# io-pack-3-3.net
KiCad netlist of a schematic drawn in EAGLE
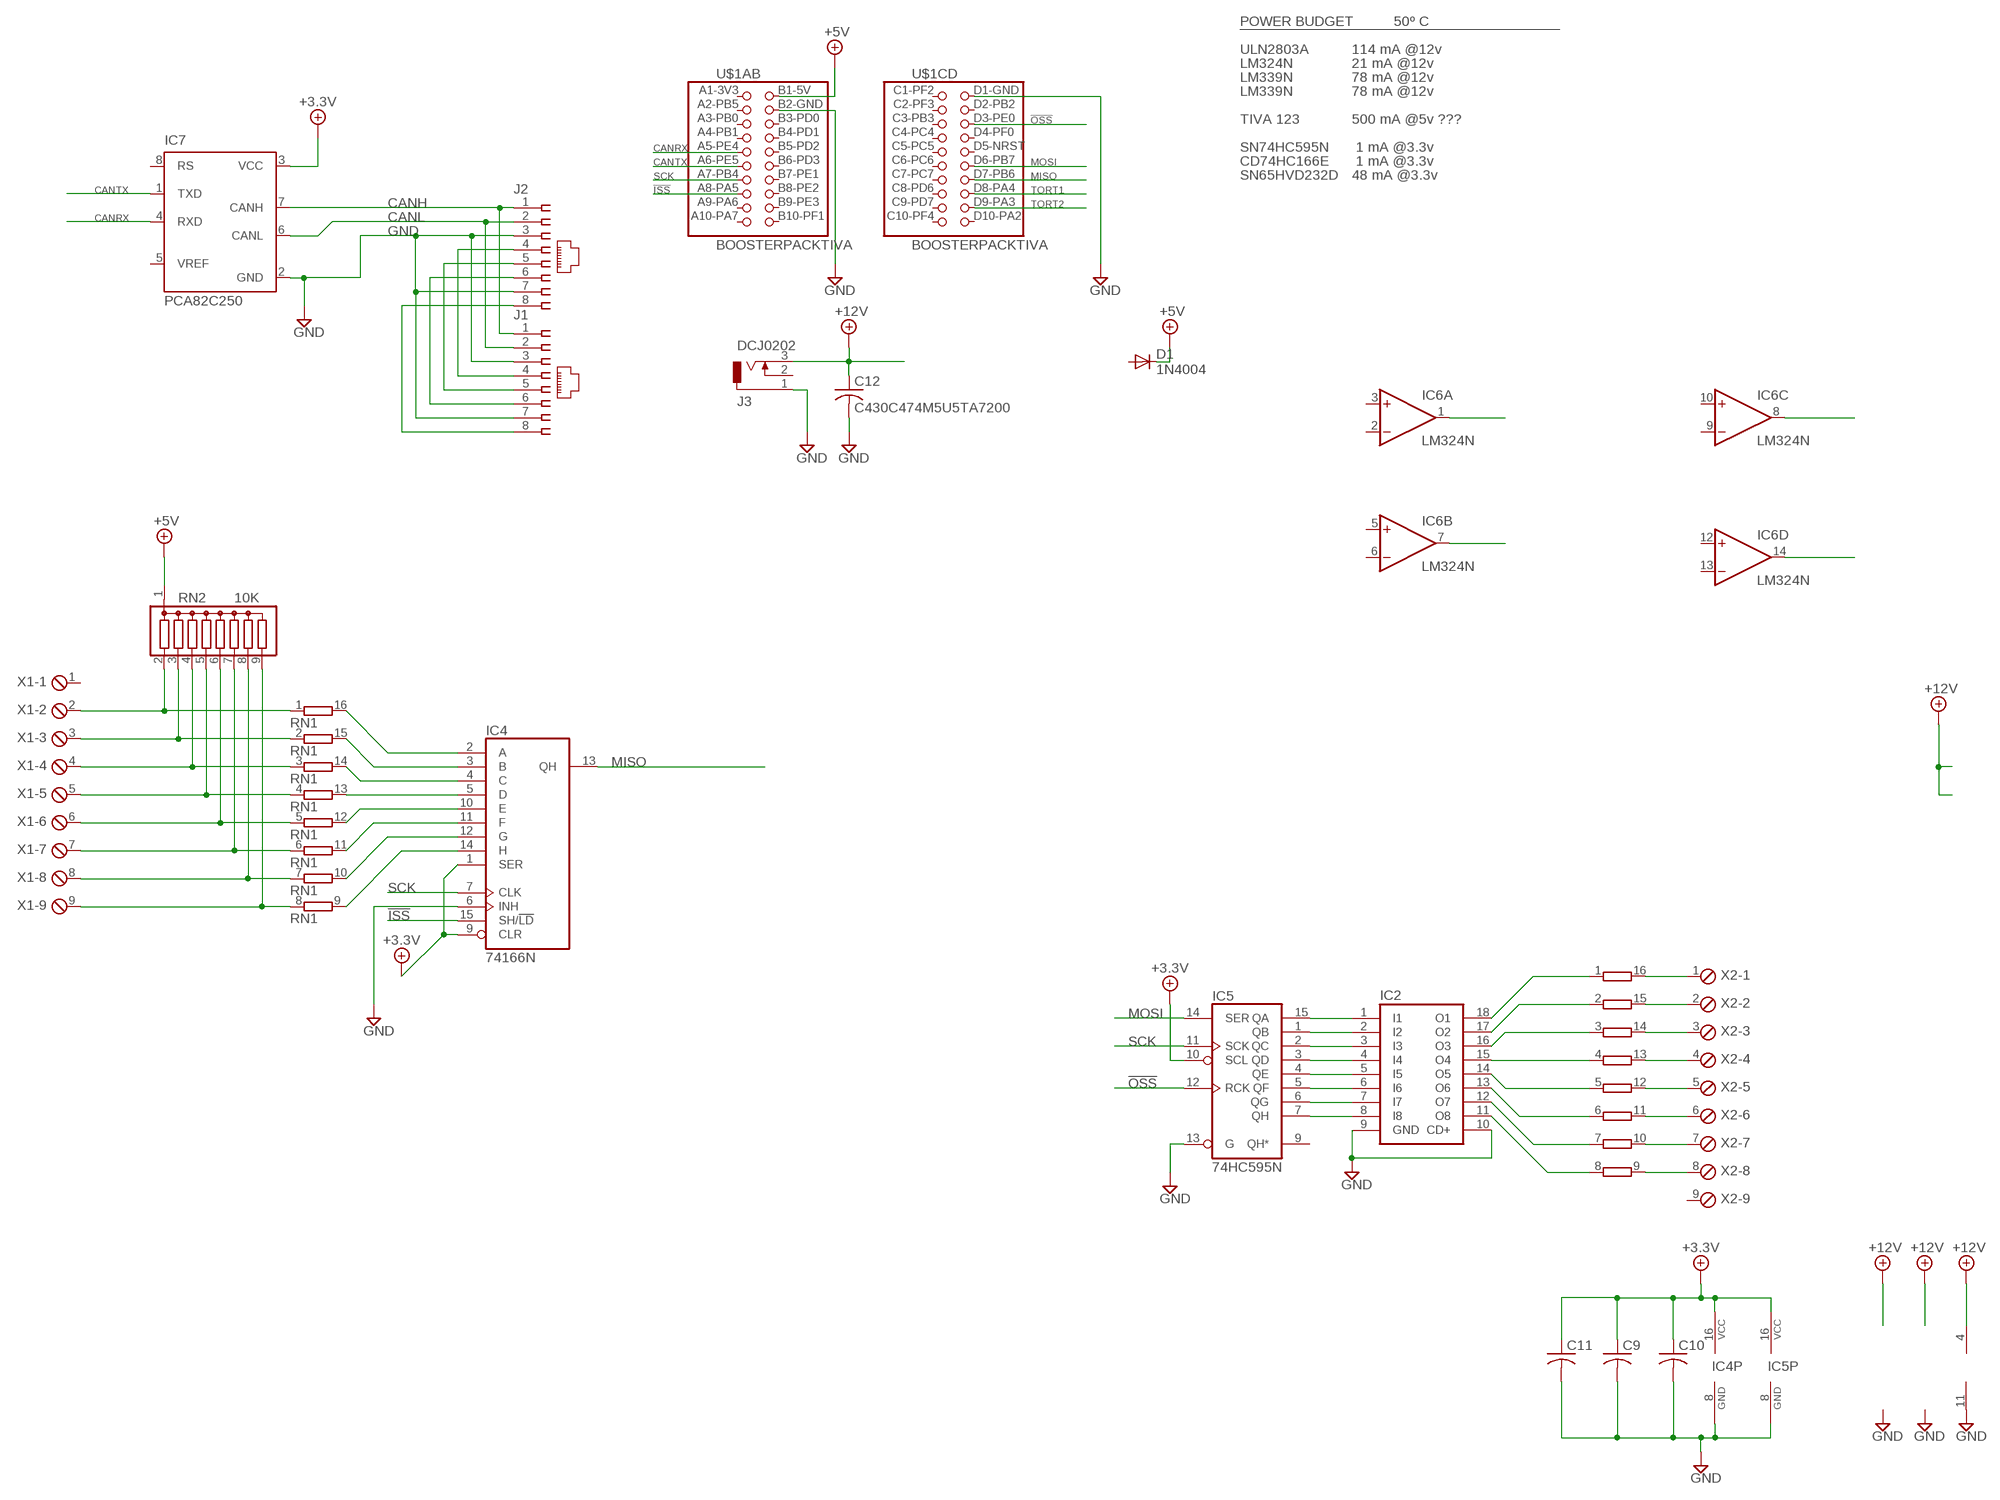
[diagram p0: schematic, sheet 1]

(export (version "E")
  (design (tool "Eeschema 10.0.6"))
  (components
    (comp (ref "C9")
      (value "C-US050-025X075")
      (footprint "eagle-import:C050-025X075")
      (libsource (lib "eagle-import") (part "C-US050-025X075"))
    )
    (comp (ref "C10")
      (value "C-US050-025X075")
      (footprint "eagle-import:C050-025X075")
      (libsource (lib "eagle-import") (part "C-US050-025X075"))
    )
    (comp (ref "C11")
      (value "C-US050-025X075")
      (footprint "eagle-import:C050-025X075")
      (libsource (lib "eagle-import") (part "C-US050-025X075"))
    )
    (comp (ref "C12")
      (value "C430C474M5U5TA7200")
      (footprint "eagle-import:C075-032X103")
      (libsource (lib "eagle-import") (part "C-US075-032X103"))
    )
    (comp (ref "D1")
      (value "1N4004")
      (footprint "eagle-import:DO41-10")
      (libsource (lib "eagle-import") (part "1N4004"))
    )
    (comp (ref "IC2")
      (value "ULN2803A")
      (footprint "eagle-import:DIL18")
      (libsource (lib "eagle-import") (part "ULN2803A"))
    )
    (comp (ref "IC4")
      (value "74166N")
      (footprint "eagle-import:DIL16")
      (libsource (lib "eagle-import") (part "74166N"))
    )
    (comp (ref "IC5")
      (value "74HC595N")
      (footprint "eagle-import:DIL16")
      (libsource (lib "eagle-import") (part "74595NLS"))
    )
    (comp (ref "IC6")
      (value "LM324N")
      (footprint "eagle-import:DIL14")
      (libsource (lib "eagle-import") (part "LM324N"))
    )
    (comp (ref "IC7")
      (value "PCA82C250")
      (footprint "eagle-import:DIL08")
      (libsource (lib "eagle-import") (part "PCA82C250"))
    )
    (comp (ref "J1")
      (value "555164-1")
      (footprint "eagle-import:555164-1")
      (libsource (lib "eagle-import") (part "555164-1"))
    )
    (comp (ref "J2")
      (value "555164-1")
      (footprint "eagle-import:555164-1")
      (libsource (lib "eagle-import") (part "555164-1"))
    )
    (comp (ref "J3")
      (value "DCJ0202")
      (footprint "eagle-import:DCJ0202")
      (libsource (lib "eagle-import") (part "DCJ0202"))
    )
    (comp (ref "RN1")
      (value "8R-P")
      (footprint "eagle-import:DIL16")
      (libsource (lib "eagle-import") (part "8R-P"))
    )
    (comp (ref "RN2")
      (value "10K")
      (footprint "eagle-import:SIL9")
      (libsource (lib "eagle-import") (part "G08R"))
    )
    (comp (ref "RN3")
      (value "8R-P")
      (footprint "eagle-import:DIL16")
      (libsource (lib "eagle-import") (part "8R-P"))
    )
    (comp (ref "U$1")
      (value "BOOSTERPACKTIVA")
      (footprint "eagle-import:BOOSTERPACK-TIVA")
      (libsource (lib "eagle-import") (part "BOOSTERPACKTIVA"))
    )
    (comp (ref "X1")
      (value "MPT9")
      (footprint "eagle-import:9POL254")
      (libsource (lib "eagle-import") (part "MPT9"))
    )
    (comp (ref "X2")
      (value "MPT9")
      (footprint "eagle-import:9POL254")
      (libsource (lib "eagle-import") (part "MPT9"))
    )
  )
  (nets
    (net (code "1") (name "+3.3V") (class "Default")
      (node (ref "C10") (pin "1") (pinfunction "1_1") (pintype "passive"))
      (node (ref "C11") (pin "1") (pinfunction "1_1") (pintype "passive"))
      (node (ref "C9") (pin "1") (pinfunction "1_1") (pintype "passive"))
      (node (ref "IC4") (pin "1") (pinfunction "SER_1") (pintype "input"))
      (node (ref "IC4") (pin "16") (pinfunction "VCC_16") (pintype "power_in"))
      (node (ref "IC4") (pin "9") (pinfunction "CLR_9") (pintype "input"))
      (node (ref "IC5") (pin "10") (pinfunction "SCL_10") (pintype "input"))
      (node (ref "IC5") (pin "16") (pinfunction "VCC_16") (pintype "power_in"))
      (node (ref "IC7") (pin "3") (pinfunction "VCC_3") (pintype "power_in"))
    )
    (net (code "2") (name "+5V") (class "Default")
      (node (ref "D1") (pin "C") (pinfunction "C_C") (pintype "passive"))
      (node (ref "RN2") (pin "1") (pinfunction "1_1") (pintype "passive"))
      (node (ref "U$1") (pin "B1-5V") (pinfunction "2_B1-5V") (pintype "passive"))
    )
    (net (code "3") (name "+12V") (class "Default")
      (node (ref "C12") (pin "1") (pinfunction "1_1") (pintype "passive"))
      (node (ref "IC6") (pin "4") (pinfunction "V+_4") (pintype "power_in"))
      (node (ref "J3") (pin "3") (pinfunction "3_3") (pintype "passive"))
    )
    (net (code "4") (name "/CANH") (class "Default")
      (node (ref "IC7") (pin "7") (pinfunction "CANH_7") (pintype "bidirectional"))
      (node (ref "J1") (pin "1") (pinfunction "1_1") (pintype "passive"))
      (node (ref "J2") (pin "1") (pinfunction "1_1") (pintype "passive"))
    )
    (net (code "5") (name "/CANL") (class "Default")
      (node (ref "IC7") (pin "6") (pinfunction "CANL_6") (pintype "bidirectional"))
      (node (ref "J1") (pin "2") (pinfunction "2_2") (pintype "passive"))
      (node (ref "J2") (pin "2") (pinfunction "2_2") (pintype "passive"))
    )
    (net (code "6") (name "/CANRX") (class "Default")
      (node (ref "IC7") (pin "4") (pinfunction "RXD_4") (pintype "output"))
      (node (ref "U$1") (pin "A5-PE4") (pinfunction "9_A5-PE4") (pintype "passive"))
    )
    (net (code "7") (name "/CANTX") (class "Default")
      (node (ref "IC7") (pin "1") (pinfunction "TXD_1") (pintype "input"))
      (node (ref "U$1") (pin "A6-PE5") (pinfunction "11_A6-PE5") (pintype "passive"))
    )
    (net (code "8") (name "/MISO") (class "Default")
      (node (ref "IC4") (pin "13") (pinfunction "QH_13") (pintype "output"))
      (node (ref "U$1") (pin "D7-PB6") (pinfunction "14_D7-PB6") (pintype "passive"))
    )
    (net (code "9") (name "/MOSI") (class "Default")
      (node (ref "IC5") (pin "14") (pinfunction "SER_14") (pintype "input"))
      (node (ref "U$1") (pin "D6-PB7") (pinfunction "12_D6-PB7") (pintype "passive"))
    )
    (net (code "10") (name "/SCK") (class "Default")
      (node (ref "IC4") (pin "7") (pinfunction "CLK_7") (pintype "input"))
      (node (ref "IC5") (pin "11") (pinfunction "SCK_11") (pintype "input"))
      (node (ref "U$1") (pin "A7-PB4") (pinfunction "13_A7-PB4") (pintype "passive"))
    )
    (net (code "11") (name "/TORT1") (class "Default")
      (node (ref "U$1") (pin "D8-PA4") (pinfunction "16_D8-PA4") (pintype "passive"))
    )
    (net (code "12") (name "/TORT2") (class "Default")
      (node (ref "U$1") (pin "D9-PA3") (pinfunction "18_D9-PA3") (pintype "passive"))
    )
    (net (code "13") (name "/~{ISS}") (class "Default")
      (node (ref "IC4") (pin "15") (pinfunction "SH/~{LD}_15") (pintype "input"))
      (node (ref "U$1") (pin "A8-PA5") (pinfunction "15_A8-PA5") (pintype "passive"))
    )
    (net (code "14") (name "/~{OSS}") (class "Default")
      (node (ref "IC5") (pin "12") (pinfunction "RCK_12") (pintype "input"))
      (node (ref "U$1") (pin "D3-PE0") (pinfunction "6_D3-PE0") (pintype "passive"))
    )
    (net (code "15") (name "GND") (class "Default")
      (node (ref "C10") (pin "2") (pinfunction "2_2") (pintype "passive"))
      (node (ref "C11") (pin "2") (pinfunction "2_2") (pintype "passive"))
      (node (ref "C12") (pin "2") (pinfunction "2_2") (pintype "passive"))
      (node (ref "C9") (pin "2") (pinfunction "2_2") (pintype "passive"))
      (node (ref "IC2") (pin "10") (pinfunction "CD+_10") (pintype "passive"))
      (node (ref "IC2") (pin "9") (pinfunction "GND_9") (pintype "power_in"))
      (node (ref "IC4") (pin "6") (pinfunction "INH_6") (pintype "input"))
      (node (ref "IC4") (pin "8") (pinfunction "GND_8") (pintype "power_in"))
      (node (ref "IC5") (pin "13") (pinfunction "G_13") (pintype "input"))
      (node (ref "IC5") (pin "8") (pinfunction "GND_8") (pintype "power_in"))
      (node (ref "IC6") (pin "11") (pinfunction "V-_11") (pintype "power_in"))
      (node (ref "IC7") (pin "2") (pinfunction "GND_2") (pintype "power_in"))
      (node (ref "J1") (pin "3") (pinfunction "3_3") (pintype "passive"))
      (node (ref "J1") (pin "7") (pinfunction "7_7") (pintype "passive"))
      (node (ref "J2") (pin "3") (pinfunction "3_3") (pintype "passive"))
      (node (ref "J2") (pin "7") (pinfunction "7_7") (pintype "passive"))
      (node (ref "J3") (pin "1") (pinfunction "1_1") (pintype "passive"))
      (node (ref "U$1") (pin "B2-GND") (pinfunction "4_B2-GND") (pintype "passive"))
      (node (ref "U$1") (pin "D1-GND") (pinfunction "2_D1-GND") (pintype "passive"))
    )
    (net (code "16") (name "Net-(IC2-I1)") (class "Default")
      (node (ref "IC2") (pin "1") (pinfunction "I1_1") (pintype "input"))
      (node (ref "IC5") (pin "15") (pinfunction "QA_15") (pintype "tri_state"))
    )
    (net (code "17") (name "Net-(IC2-I2)") (class "Default")
      (node (ref "IC2") (pin "2") (pinfunction "I2_2") (pintype "input"))
      (node (ref "IC5") (pin "1") (pinfunction "QB_1") (pintype "tri_state"))
    )
    (net (code "18") (name "Net-(IC2-I3)") (class "Default")
      (node (ref "IC2") (pin "3") (pinfunction "I3_3") (pintype "input"))
      (node (ref "IC5") (pin "2") (pinfunction "QC_2") (pintype "tri_state"))
    )
    (net (code "19") (name "Net-(IC2-I4)") (class "Default")
      (node (ref "IC2") (pin "4") (pinfunction "I4_4") (pintype "input"))
      (node (ref "IC5") (pin "3") (pinfunction "QD_3") (pintype "tri_state"))
    )
    (net (code "20") (name "Net-(IC2-I5)") (class "Default")
      (node (ref "IC2") (pin "5") (pinfunction "I5_5") (pintype "input"))
      (node (ref "IC5") (pin "4") (pinfunction "QE_4") (pintype "tri_state"))
    )
    (net (code "21") (name "Net-(IC2-I6)") (class "Default")
      (node (ref "IC2") (pin "6") (pinfunction "I6_6") (pintype "input"))
      (node (ref "IC5") (pin "5") (pinfunction "QF_5") (pintype "tri_state"))
    )
    (net (code "22") (name "Net-(IC2-I7)") (class "Default")
      (node (ref "IC2") (pin "7") (pinfunction "I7_7") (pintype "input"))
      (node (ref "IC5") (pin "6") (pinfunction "QG_6") (pintype "tri_state"))
    )
    (net (code "23") (name "Net-(IC2-I8)") (class "Default")
      (node (ref "IC2") (pin "8") (pinfunction "I8_8") (pintype "input"))
      (node (ref "IC5") (pin "7") (pinfunction "QH_7") (pintype "tri_state"))
    )
    (net (code "24") (name "Net-(IC2-O1)") (class "Default")
      (node (ref "IC2") (pin "18") (pinfunction "O1_18") (pintype "open_collector"))
      (node (ref "RN3") (pin "1") (pinfunction "1_1") (pintype "passive"))
    )
    (net (code "25") (name "Net-(IC2-O2)") (class "Default")
      (node (ref "IC2") (pin "17") (pinfunction "O2_17") (pintype "open_collector"))
      (node (ref "RN3") (pin "2") (pinfunction "1_2") (pintype "passive"))
    )
    (net (code "26") (name "Net-(IC2-O3)") (class "Default")
      (node (ref "IC2") (pin "16") (pinfunction "O3_16") (pintype "open_collector"))
      (node (ref "RN3") (pin "3") (pinfunction "1_3") (pintype "passive"))
    )
    (net (code "27") (name "Net-(IC2-O4)") (class "Default")
      (node (ref "IC2") (pin "15") (pinfunction "O4_15") (pintype "open_collector"))
      (node (ref "RN3") (pin "4") (pinfunction "1_4") (pintype "passive"))
    )
    (net (code "28") (name "Net-(IC2-O5)") (class "Default")
      (node (ref "IC2") (pin "14") (pinfunction "O5_14") (pintype "open_collector"))
      (node (ref "RN3") (pin "5") (pinfunction "1_5") (pintype "passive"))
    )
    (net (code "29") (name "Net-(IC2-O6)") (class "Default")
      (node (ref "IC2") (pin "13") (pinfunction "O6_13") (pintype "open_collector"))
      (node (ref "RN3") (pin "6") (pinfunction "1_6") (pintype "passive"))
    )
    (net (code "30") (name "Net-(IC2-O7)") (class "Default")
      (node (ref "IC2") (pin "12") (pinfunction "O7_12") (pintype "open_collector"))
      (node (ref "RN3") (pin "7") (pinfunction "1_7") (pintype "passive"))
    )
    (net (code "31") (name "Net-(IC2-O8)") (class "Default")
      (node (ref "IC2") (pin "11") (pinfunction "O8_11") (pintype "open_collector"))
      (node (ref "RN3") (pin "8") (pinfunction "1_8") (pintype "passive"))
    )
    (net (code "32") (name "Net-(IC4A-A)") (class "Default")
      (node (ref "IC4") (pin "2") (pinfunction "A_2") (pintype "input"))
      (node (ref "RN1") (pin "16") (pinfunction "2_16") (pintype "passive"))
    )
    (net (code "33") (name "Net-(IC4A-B)") (class "Default")
      (node (ref "IC4") (pin "3") (pinfunction "B_3") (pintype "input"))
      (node (ref "RN1") (pin "15") (pinfunction "2_15") (pintype "passive"))
    )
    (net (code "34") (name "Net-(IC4A-C)") (class "Default")
      (node (ref "IC4") (pin "4") (pinfunction "C_4") (pintype "input"))
      (node (ref "RN1") (pin "14") (pinfunction "2_14") (pintype "passive"))
    )
    (net (code "35") (name "Net-(IC4A-D)") (class "Default")
      (node (ref "IC4") (pin "5") (pinfunction "D_5") (pintype "input"))
      (node (ref "RN1") (pin "13") (pinfunction "2_13") (pintype "passive"))
    )
    (net (code "36") (name "Net-(IC4A-E)") (class "Default")
      (node (ref "IC4") (pin "10") (pinfunction "E_10") (pintype "input"))
      (node (ref "RN1") (pin "12") (pinfunction "2_12") (pintype "passive"))
    )
    (net (code "37") (name "Net-(IC4A-F)") (class "Default")
      (node (ref "IC4") (pin "11") (pinfunction "F_11") (pintype "input"))
      (node (ref "RN1") (pin "11") (pinfunction "2_11") (pintype "passive"))
    )
    (net (code "38") (name "Net-(IC4A-G)") (class "Default")
      (node (ref "IC4") (pin "12") (pinfunction "G_12") (pintype "input"))
      (node (ref "RN1") (pin "10") (pinfunction "2_10") (pintype "passive"))
    )
    (net (code "39") (name "Net-(IC4A-H)") (class "Default")
      (node (ref "IC4") (pin "14") (pinfunction "H_14") (pintype "input"))
      (node (ref "RN1") (pin "9") (pinfunction "2_9") (pintype "passive"))
    )
    (net (code "40") (name "Net-(J1-Pad4)") (class "Default")
      (node (ref "J1") (pin "4") (pinfunction "4_4") (pintype "passive"))
      (node (ref "J2") (pin "4") (pinfunction "4_4") (pintype "passive"))
    )
    (net (code "41") (name "Net-(J1-Pad5)") (class "Default")
      (node (ref "J1") (pin "5") (pinfunction "5_5") (pintype "passive"))
      (node (ref "J2") (pin "5") (pinfunction "5_5") (pintype "passive"))
    )
    (net (code "42") (name "Net-(J1-Pad6)") (class "Default")
      (node (ref "J1") (pin "6") (pinfunction "6_6") (pintype "passive"))
      (node (ref "J2") (pin "6") (pinfunction "6_6") (pintype "passive"))
    )
    (net (code "43") (name "Net-(J1-Pad8)") (class "Default")
      (node (ref "J1") (pin "8") (pinfunction "8_8") (pintype "passive"))
      (node (ref "J2") (pin "8") (pinfunction "8_8") (pintype "passive"))
    )
    (net (code "44") (name "Net-(RN1B-1)") (class "Default")
      (node (ref "RN1") (pin "2") (pinfunction "1_2") (pintype "passive"))
      (node (ref "RN2") (pin "3") (pinfunction "3_3") (pintype "passive"))
      (node (ref "X1") (pin "3") (pinfunction "1_3") (pintype "passive"))
    )
    (net (code "45") (name "Net-(RN1C-1)") (class "Default")
      (node (ref "RN1") (pin "3") (pinfunction "1_3") (pintype "passive"))
      (node (ref "RN2") (pin "4") (pinfunction "4_4") (pintype "passive"))
      (node (ref "X1") (pin "4") (pinfunction "1_4") (pintype "passive"))
    )
    (net (code "46") (name "Net-(RN1D-1)") (class "Default")
      (node (ref "RN1") (pin "4") (pinfunction "1_4") (pintype "passive"))
      (node (ref "RN2") (pin "5") (pinfunction "5_5") (pintype "passive"))
      (node (ref "X1") (pin "5") (pinfunction "1_5") (pintype "passive"))
    )
    (net (code "47") (name "Net-(RN1E-1)") (class "Default")
      (node (ref "RN1") (pin "5") (pinfunction "1_5") (pintype "passive"))
      (node (ref "RN2") (pin "6") (pinfunction "6_6") (pintype "passive"))
      (node (ref "X1") (pin "6") (pinfunction "1_6") (pintype "passive"))
    )
    (net (code "48") (name "Net-(RN1F-1)") (class "Default")
      (node (ref "RN1") (pin "6") (pinfunction "1_6") (pintype "passive"))
      (node (ref "RN2") (pin "7") (pinfunction "7_7") (pintype "passive"))
      (node (ref "X1") (pin "7") (pinfunction "1_7") (pintype "passive"))
    )
    (net (code "49") (name "Net-(RN1G-1)") (class "Default")
      (node (ref "RN1") (pin "7") (pinfunction "1_7") (pintype "passive"))
      (node (ref "RN2") (pin "8") (pinfunction "8_8") (pintype "passive"))
      (node (ref "X1") (pin "8") (pinfunction "1_8") (pintype "passive"))
    )
    (net (code "50") (name "Net-(RN1H-1)") (class "Default")
      (node (ref "RN1") (pin "8") (pinfunction "1_8") (pintype "passive"))
      (node (ref "RN2") (pin "9") (pinfunction "9_9") (pintype "passive"))
      (node (ref "X1") (pin "9") (pinfunction "1_9") (pintype "passive"))
    )
    (net (code "51") (name "Net-(RN3A-2)") (class "Default")
      (node (ref "RN3") (pin "16") (pinfunction "2_16") (pintype "passive"))
      (node (ref "X2") (pin "1") (pinfunction "1_1") (pintype "passive"))
    )
    (net (code "52") (name "Net-(RN3B-2)") (class "Default")
      (node (ref "RN3") (pin "15") (pinfunction "2_15") (pintype "passive"))
      (node (ref "X2") (pin "2") (pinfunction "1_2") (pintype "passive"))
    )
    (net (code "53") (name "Net-(RN3C-2)") (class "Default")
      (node (ref "RN3") (pin "14") (pinfunction "2_14") (pintype "passive"))
      (node (ref "X2") (pin "3") (pinfunction "1_3") (pintype "passive"))
    )
    (net (code "54") (name "Net-(RN3D-2)") (class "Default")
      (node (ref "RN3") (pin "13") (pinfunction "2_13") (pintype "passive"))
      (node (ref "X2") (pin "4") (pinfunction "1_4") (pintype "passive"))
    )
    (net (code "55") (name "Net-(RN3E-2)") (class "Default")
      (node (ref "RN3") (pin "12") (pinfunction "2_12") (pintype "passive"))
      (node (ref "X2") (pin "5") (pinfunction "1_5") (pintype "passive"))
    )
    (net (code "56") (name "Net-(RN3F-2)") (class "Default")
      (node (ref "RN3") (pin "11") (pinfunction "2_11") (pintype "passive"))
      (node (ref "X2") (pin "6") (pinfunction "1_6") (pintype "passive"))
    )
    (net (code "57") (name "Net-(RN3G-2)") (class "Default")
      (node (ref "RN3") (pin "10") (pinfunction "2_10") (pintype "passive"))
      (node (ref "X2") (pin "7") (pinfunction "1_7") (pintype "passive"))
    )
    (net (code "58") (name "Net-(RN3H-2)") (class "Default")
      (node (ref "RN3") (pin "9") (pinfunction "2_9") (pintype "passive"))
      (node (ref "X2") (pin "8") (pinfunction "1_8") (pintype "passive"))
    )
    (net (code "59") (name "Net-(X1B-1)") (class "Default")
      (node (ref "RN1") (pin "1") (pinfunction "1_1") (pintype "passive"))
      (node (ref "RN2") (pin "2") (pinfunction "2_2") (pintype "passive"))
      (node (ref "X1") (pin "2") (pinfunction "1_2") (pintype "passive"))
    )
    (net (code "60") (name "unconnected-(D1-PadA)") (class "Default")
      (node (ref "D1") (pin "A") (pinfunction "A_A") (pintype "passive"))
    )
    (net (code "61") (name "unconnected-(IC5A-QH*-Pad9)") (class "Default")
      (node (ref "IC5") (pin "9") (pinfunction "QH*_9") (pintype "tri_state"))
    )
    (net (code "62") (name "unconnected-(IC6A-+IN-Pad3)") (class "Default")
      (node (ref "IC6") (pin "3") (pinfunction "+IN_3") (pintype "input"))
    )
    (net (code "63") (name "unconnected-(IC6A--IN-Pad2)") (class "Default")
      (node (ref "IC6") (pin "2") (pinfunction "-IN_2") (pintype "input"))
    )
    (net (code "64") (name "unconnected-(IC6A-OUT-Pad1)") (class "Default")
      (node (ref "IC6") (pin "1") (pinfunction "OUT_1") (pintype "output"))
    )
    (net (code "65") (name "unconnected-(IC6B-+IN-Pad5)") (class "Default")
      (node (ref "IC6") (pin "5") (pinfunction "+IN_5") (pintype "input"))
    )
    (net (code "66") (name "unconnected-(IC6B--IN-Pad6)") (class "Default")
      (node (ref "IC6") (pin "6") (pinfunction "-IN_6") (pintype "input"))
    )
    (net (code "67") (name "unconnected-(IC6B-OUT-Pad7)") (class "Default")
      (node (ref "IC6") (pin "7") (pinfunction "OUT_7") (pintype "output"))
    )
    (net (code "68") (name "unconnected-(IC6C-+IN-Pad10)") (class "Default")
      (node (ref "IC6") (pin "10") (pinfunction "+IN_10") (pintype "input"))
    )
    (net (code "69") (name "unconnected-(IC6C--IN-Pad9)") (class "Default")
      (node (ref "IC6") (pin "9") (pinfunction "-IN_9") (pintype "input"))
    )
    (net (code "70") (name "unconnected-(IC6C-OUT-Pad8)") (class "Default")
      (node (ref "IC6") (pin "8") (pinfunction "OUT_8") (pintype "output"))
    )
    (net (code "71") (name "unconnected-(IC6D-+IN-Pad12)") (class "Default")
      (node (ref "IC6") (pin "12") (pinfunction "+IN_12") (pintype "input"))
    )
    (net (code "72") (name "unconnected-(IC6D--IN-Pad13)") (class "Default")
      (node (ref "IC6") (pin "13") (pinfunction "-IN_13") (pintype "input"))
    )
    (net (code "73") (name "unconnected-(IC6D-OUT-Pad14)") (class "Default")
      (node (ref "IC6") (pin "14") (pinfunction "OUT_14") (pintype "output"))
    )
    (net (code "74") (name "unconnected-(IC7-RS-Pad8)") (class "Default")
      (node (ref "IC7") (pin "8") (pinfunction "RS_8") (pintype "input"))
    )
    (net (code "75") (name "unconnected-(IC7-VREF-Pad5)") (class "Default")
      (node (ref "IC7") (pin "5") (pinfunction "VREF_5") (pintype "output"))
    )
    (net (code "76") (name "unconnected-(J3-Pad2)") (class "Default")
      (node (ref "J3") (pin "2") (pinfunction "2_2") (pintype "passive"))
    )
    (net (code "77") (name "unconnected-(U$1A-1-PadA1-3V3)") (class "Default")
      (node (ref "U$1") (pin "A1-3V3") (pinfunction "1_A1-3V3") (pintype "passive"))
    )
    (net (code "78") (name "unconnected-(U$1A-3-PadA2-PB5)") (class "Default")
      (node (ref "U$1") (pin "A2-PB5") (pinfunction "3_A2-PB5") (pintype "passive"))
    )
    (net (code "79") (name "unconnected-(U$1A-5-PadA3-PB0)") (class "Default")
      (node (ref "U$1") (pin "A3-PB0") (pinfunction "5_A3-PB0") (pintype "passive"))
    )
    (net (code "80") (name "unconnected-(U$1A-6-PadB3-PD0)") (class "Default")
      (node (ref "U$1") (pin "B3-PD0") (pinfunction "6_B3-PD0") (pintype "passive"))
    )
    (net (code "81") (name "unconnected-(U$1A-7-PadA4-PB1)") (class "Default")
      (node (ref "U$1") (pin "A4-PB1") (pinfunction "7_A4-PB1") (pintype "passive"))
    )
    (net (code "82") (name "unconnected-(U$1A-8-PadB4-PD1)") (class "Default")
      (node (ref "U$1") (pin "B4-PD1") (pinfunction "8_B4-PD1") (pintype "passive"))
    )
    (net (code "83") (name "unconnected-(U$1A-10-PadB5-PD2)") (class "Default")
      (node (ref "U$1") (pin "B5-PD2") (pinfunction "10_B5-PD2") (pintype "passive"))
    )
    (net (code "84") (name "unconnected-(U$1A-12-PadB6-PD3)") (class "Default")
      (node (ref "U$1") (pin "B6-PD3") (pinfunction "12_B6-PD3") (pintype "passive"))
    )
    (net (code "85") (name "unconnected-(U$1A-14-PadB7-PE1)") (class "Default")
      (node (ref "U$1") (pin "B7-PE1") (pinfunction "14_B7-PE1") (pintype "passive"))
    )
    (net (code "86") (name "unconnected-(U$1A-16-PadB8-PE2)") (class "Default")
      (node (ref "U$1") (pin "B8-PE2") (pinfunction "16_B8-PE2") (pintype "passive"))
    )
    (net (code "87") (name "unconnected-(U$1A-17-PadA9-PA6)") (class "Default")
      (node (ref "U$1") (pin "A9-PA6") (pinfunction "17_A9-PA6") (pintype "passive"))
    )
    (net (code "88") (name "unconnected-(U$1A-18-PadB9-PE3)") (class "Default")
      (node (ref "U$1") (pin "B9-PE3") (pinfunction "18_B9-PE3") (pintype "passive"))
    )
    (net (code "89") (name "unconnected-(U$1A-19-PadA10-PA7)") (class "Default")
      (node (ref "U$1") (pin "A10-PA7") (pinfunction "19_A10-PA7") (pintype "passive"))
    )
    (net (code "90") (name "unconnected-(U$1A-20-PadB10-PF1)") (class "Default")
      (node (ref "U$1") (pin "B10-PF1") (pinfunction "20_B10-PF1") (pintype "passive"))
    )
    (net (code "91") (name "unconnected-(U$1B-1-PadC1-PF2)") (class "Default")
      (node (ref "U$1") (pin "C1-PF2") (pinfunction "1_C1-PF2") (pintype "passive"))
    )
    (net (code "92") (name "unconnected-(U$1B-3-PadC2-PF3)") (class "Default")
      (node (ref "U$1") (pin "C2-PF3") (pinfunction "3_C2-PF3") (pintype "passive"))
    )
    (net (code "93") (name "unconnected-(U$1B-4-PadD2-PB2)") (class "Default")
      (node (ref "U$1") (pin "D2-PB2") (pinfunction "4_D2-PB2") (pintype "passive"))
    )
    (net (code "94") (name "unconnected-(U$1B-5-PadC3-PB3)") (class "Default")
      (node (ref "U$1") (pin "C3-PB3") (pinfunction "5_C3-PB3") (pintype "passive"))
    )
    (net (code "95") (name "unconnected-(U$1B-7-PadC4-PC4)") (class "Default")
      (node (ref "U$1") (pin "C4-PC4") (pinfunction "7_C4-PC4") (pintype "passive"))
    )
    (net (code "96") (name "unconnected-(U$1B-8-PadD4-PF0)") (class "Default")
      (node (ref "U$1") (pin "D4-PF0") (pinfunction "8_D4-PF0") (pintype "passive"))
    )
    (net (code "97") (name "unconnected-(U$1B-9-PadC5-PC5)") (class "Default")
      (node (ref "U$1") (pin "C5-PC5") (pinfunction "9_C5-PC5") (pintype "passive"))
    )
    (net (code "98") (name "unconnected-(U$1B-10-PadD5-NRST)") (class "Default")
      (node (ref "U$1") (pin "D5-NRST") (pinfunction "10_D5-NRST") (pintype "passive"))
    )
    (net (code "99") (name "unconnected-(U$1B-11-PadC6-PC6)") (class "Default")
      (node (ref "U$1") (pin "C6-PC6") (pinfunction "11_C6-PC6") (pintype "passive"))
    )
    (net (code "100") (name "unconnected-(U$1B-13-PadC7-PC7)") (class "Default")
      (node (ref "U$1") (pin "C7-PC7") (pinfunction "13_C7-PC7") (pintype "passive"))
    )
    (net (code "101") (name "unconnected-(U$1B-15-PadC8-PD6)") (class "Default")
      (node (ref "U$1") (pin "C8-PD6") (pinfunction "15_C8-PD6") (pintype "passive"))
    )
    (net (code "102") (name "unconnected-(U$1B-17-PadC9-PD7)") (class "Default")
      (node (ref "U$1") (pin "C9-PD7") (pinfunction "17_C9-PD7") (pintype "passive"))
    )
    (net (code "103") (name "unconnected-(U$1B-19-PadC10-PF4)") (class "Default")
      (node (ref "U$1") (pin "C10-PF4") (pinfunction "19_C10-PF4") (pintype "passive"))
    )
    (net (code "104") (name "unconnected-(U$1B-20-PadD10-PA2)") (class "Default")
      (node (ref "U$1") (pin "D10-PA2") (pinfunction "20_D10-PA2") (pintype "passive"))
    )
    (net (code "105") (name "unconnected-(X1-Pad1)") (class "Default")
      (node (ref "X1") (pin "1") (pinfunction "1_1") (pintype "passive"))
    )
    (net (code "106") (name "unconnected-(X2I-1-Pad9)") (class "Default")
      (node (ref "X2") (pin "9") (pinfunction "1_9") (pintype "passive"))
    )
  )
)
